# UPCH.net
KiCad netlist of a schematic drawn in EAGLE
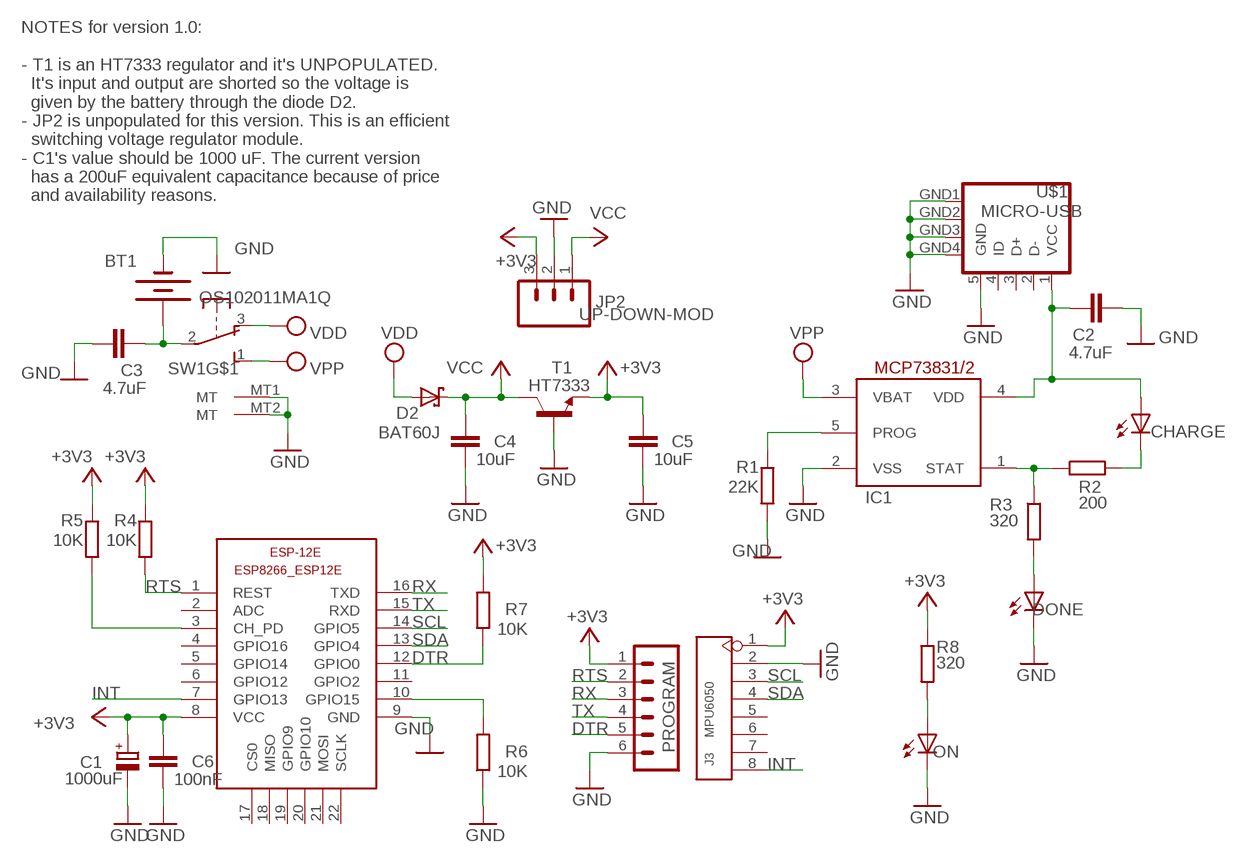
[diagram p0: schematic, sheet 1]

(export (version "E")
  (design (tool "Eeschema 10.0.6"))
  (components
    (comp (ref "BT1")
      (value "BATTERY24.5MM")
      (footprint "eagle-import:BATTCON_24.5MM")
      (libsource (lib "eagle-import") (part "BATTERY24.5MM"))
    )
    (comp (ref "C1")
      (value "1000uF")
      (footprint "eagle-import:D_7343-31W")
      (libsource (lib "eagle-import") (part "CPOL-EUD/7343-31W"))
    )
    (comp (ref "C2")
      (value "4.7uF")
      (footprint "eagle-import:C1206")
      (libsource (lib "eagle-import") (part "C-EUC1206"))
    )
    (comp (ref "C3")
      (value "4.7uF")
      (footprint "eagle-import:C1206")
      (libsource (lib "eagle-import") (part "C-EUC1206"))
    )
    (comp (ref "C4")
      (value "10uF")
      (footprint "eagle-import:C1206")
      (libsource (lib "eagle-import") (part "C-EUC1206"))
    )
    (comp (ref "C5")
      (value "10uF")
      (footprint "eagle-import:C1206")
      (libsource (lib "eagle-import") (part "C-EUC1206"))
    )
    (comp (ref "C6")
      (value "100nF")
      (footprint "eagle-import:C1206")
      (libsource (lib "eagle-import") (part "C-EUC1206"))
    )
    (comp (ref "CHARGE")
      (value "LEDCHIP-LED0603")
      (footprint "eagle-import:CHIP-LED0603")
      (libsource (lib "eagle-import") (part "LEDCHIP-LED0603"))
    )
    (comp (ref "D2")
      (value "BAT60J")
      (footprint "eagle-import:SOD323_ST")
      (libsource (lib "eagle-import") (part "BAT60J"))
    )
    (comp (ref "DONE")
      (value "LEDCHIP-LED0603")
      (footprint "eagle-import:CHIP-LED0603")
      (libsource (lib "eagle-import") (part "LEDCHIP-LED0603"))
    )
    (comp (ref "ESP-12E")
      (value "ESP8266-12EESP8266-ESP12E")
      (footprint "eagle-import:ESP8266-ESP12E")
      (libsource (lib "eagle-import") (part "ESP8266-12EESP8266-ESP12E"))
    )
    (comp (ref "IC1")
      (value "MCP73831")
      (footprint "eagle-import:SOT23-5L")
      (libsource (lib "eagle-import") (part "MCP73831/OT"))
    )
    (comp (ref "J3")
      (value "MPU6050")
      (footprint "eagle-import:H8-SMD-2.54-90D")
      (fields (field (name "MPN") "F185-1108A0BZYA1"))
      (libsource (lib "eagle-import") (part "SMD-BLACK-FEMALE-HEADER(8P-2.54-90D)"))
    )
    (comp (ref "JP2")
      (value "UP-DOWN-MOD")
      (footprint "eagle-import:1X03")
      (libsource (lib "eagle-import") (part "M03PTH"))
    )
    (comp (ref "ON")
      (value "LEDCHIP-LED0603")
      (footprint "eagle-import:CHIP-LED0603")
      (libsource (lib "eagle-import") (part "LEDCHIP-LED0603"))
    )
    (comp (ref "PROGRAM")
      (value "CONN_06SILK_FEMALE_PTH")
      (footprint "eagle-import:1X06")
      (libsource (lib "eagle-import") (part "CONN_06SILK_FEMALE_PTH"))
    )
    (comp (ref "R1")
      (value "22K")
      (footprint "eagle-import:R0603")
      (libsource (lib "eagle-import") (part "R-EU_R0603"))
    )
    (comp (ref "R2")
      (value "200")
      (footprint "eagle-import:R1206")
      (libsource (lib "eagle-import") (part "R-EU_R1206"))
    )
    (comp (ref "R3")
      (value "320")
      (footprint "eagle-import:R0603")
      (libsource (lib "eagle-import") (part "R-EU_R0603"))
    )
    (comp (ref "R4")
      (value "10K")
      (footprint "eagle-import:R0603")
      (libsource (lib "eagle-import") (part "R-EU_R0603"))
    )
    (comp (ref "R5")
      (value "10K")
      (footprint "eagle-import:R0603")
      (libsource (lib "eagle-import") (part "R-EU_R0603"))
    )
    (comp (ref "R6")
      (value "10K")
      (footprint "eagle-import:R0603")
      (libsource (lib "eagle-import") (part "R-EU_R0603"))
    )
    (comp (ref "R7")
      (value "10K")
      (footprint "eagle-import:R1206")
      (libsource (lib "eagle-import") (part "R-EU_R1206"))
    )
    (comp (ref "R8")
      (value "320")
      (footprint "eagle-import:R0603")
      (libsource (lib "eagle-import") (part "R-EU_R0603"))
    )
    (comp (ref "SW1")
      (value "OS102011MA1Q")
      (footprint "eagle-import:OS102011MA1Q")
      (libsource (lib "eagle-import") (part "OS102011MA1Q"))
    )
    (comp (ref "T1")
      (value "HT7333")
      (footprint "eagle-import:SOT89-BCE")
      (libsource (lib "eagle-import") (part "-NPN-SOT89-BCE"))
    )
    (comp (ref "U$1")
      (value "MICRO-USB")
      (footprint "eagle-import:MICRO-USB")
      (libsource (lib "eagle-import") (part "MICRO-USB"))
    )
  )
  (nets
    (net (code "1") (name "+3V3") (class "Default")
      (node (ref "C1") (pin "+") (pinfunction "+_+") (pintype "passive"))
      (node (ref "C5") (pin "1") (pinfunction "1_1") (pintype "passive"))
      (node (ref "C6") (pin "1") (pinfunction "1_1") (pintype "passive"))
      (node (ref "ESP-12E") (pin "8") (pinfunction "VCC_8") (pintype "bidirectional"))
      (node (ref "J3") (pin "1") (pinfunction "1_1") (pintype "bidirectional"))
      (node (ref "JP2") (pin "3") (pinfunction "3_3") (pintype "passive"))
      (node (ref "PROGRAM") (pin "1") (pinfunction "1_1") (pintype "passive"))
      (node (ref "R4") (pin "2") (pinfunction "2_2") (pintype "passive"))
      (node (ref "R5") (pin "2") (pinfunction "2_2") (pintype "passive"))
      (node (ref "R7") (pin "2") (pinfunction "2_2") (pintype "passive"))
      (node (ref "R8") (pin "1") (pinfunction "1_1") (pintype "passive"))
      (node (ref "T1") (pin "E") (pinfunction "E_E") (pintype "passive"))
    )
    (net (code "2") (name "/DTR") (class "Default")
      (node (ref "ESP-12E") (pin "12") (pinfunction "GPIO0_12") (pintype "bidirectional"))
      (node (ref "PROGRAM") (pin "5") (pinfunction "5_5") (pintype "passive"))
      (node (ref "R7") (pin "1") (pinfunction "1_1") (pintype "passive"))
    )
    (net (code "3") (name "/INT") (class "Default")
      (node (ref "ESP-12E") (pin "7") (pinfunction "GPIO13_7") (pintype "bidirectional"))
      (node (ref "J3") (pin "8") (pinfunction "8_8") (pintype "bidirectional"))
    )
    (net (code "4") (name "/RTS") (class "Default")
      (node (ref "ESP-12E") (pin "1") (pinfunction "REST_1") (pintype "bidirectional"))
      (node (ref "PROGRAM") (pin "2") (pinfunction "2_2") (pintype "passive"))
      (node (ref "R4") (pin "1") (pinfunction "1_1") (pintype "passive"))
    )
    (net (code "5") (name "/RX") (class "Default")
      (node (ref "ESP-12E") (pin "16") (pinfunction "TXD_16") (pintype "bidirectional"))
      (node (ref "PROGRAM") (pin "3") (pinfunction "3_3") (pintype "passive"))
    )
    (net (code "6") (name "/SCL") (class "Default")
      (node (ref "ESP-12E") (pin "14") (pinfunction "GPIO5_14") (pintype "bidirectional"))
      (node (ref "J3") (pin "3") (pinfunction "3_3") (pintype "bidirectional"))
    )
    (net (code "7") (name "/SDA") (class "Default")
      (node (ref "ESP-12E") (pin "13") (pinfunction "GPIO4_13") (pintype "bidirectional"))
      (node (ref "J3") (pin "4") (pinfunction "4_4") (pintype "bidirectional"))
    )
    (net (code "8") (name "/TX") (class "Default")
      (node (ref "ESP-12E") (pin "15") (pinfunction "RXD_15") (pintype "bidirectional"))
      (node (ref "PROGRAM") (pin "4") (pinfunction "4_4") (pintype "passive"))
    )
    (net (code "9") (name "GND") (class "Default")
      (node (ref "BT1") (pin "2") (pinfunction "-_2") (pintype "power_in"))
      (node (ref "C1") (pin "-") (pinfunction "-_-") (pintype "passive"))
      (node (ref "C2") (pin "2") (pinfunction "2_2") (pintype "passive"))
      (node (ref "C3") (pin "2") (pinfunction "2_2") (pintype "passive"))
      (node (ref "C4") (pin "2") (pinfunction "2_2") (pintype "passive"))
      (node (ref "C5") (pin "2") (pinfunction "2_2") (pintype "passive"))
      (node (ref "C6") (pin "2") (pinfunction "2_2") (pintype "passive"))
      (node (ref "DONE") (pin "C") (pinfunction "C_C") (pintype "passive"))
      (node (ref "ESP-12E") (pin "9") (pinfunction "GND_9") (pintype "bidirectional"))
      (node (ref "IC1") (pin "2") (pinfunction "VSS_2") (pintype "power_in"))
      (node (ref "J3") (pin "2") (pinfunction "2_2") (pintype "bidirectional"))
      (node (ref "JP2") (pin "2") (pinfunction "2_2") (pintype "passive"))
      (node (ref "ON") (pin "C") (pinfunction "C_C") (pintype "passive"))
      (node (ref "PROGRAM") (pin "6") (pinfunction "6_6") (pintype "passive"))
      (node (ref "R1") (pin "1") (pinfunction "1_1") (pintype "passive"))
      (node (ref "R6") (pin "1") (pinfunction "1_1") (pintype "passive"))
      (node (ref "SW1") (pin "MT1") (pinfunction "MT_MT1") (pintype "passive"))
      (node (ref "SW1") (pin "MT2") (pinfunction "MT_MT2") (pintype "passive"))
      (node (ref "T1") (pin "B") (pinfunction "B_B") (pintype "passive"))
      (node (ref "U$1") (pin "5") (pinfunction "GND_5") (pintype "power_in"))
      (node (ref "U$1") (pin "GND1") (pinfunction "GND_GND1") (pintype "power_in"))
      (node (ref "U$1") (pin "GND2") (pinfunction "GND_GND2") (pintype "power_in"))
      (node (ref "U$1") (pin "GND3") (pinfunction "GND_GND3") (pintype "power_in"))
      (node (ref "U$1") (pin "GND4") (pinfunction "GND_GND4") (pintype "power_in"))
    )
    (net (code "10") (name "Net-(BT1-+)") (class "Default")
      (node (ref "BT1") (pin "1") (pinfunction "+_1") (pintype "power_in"))
      (node (ref "C3") (pin "1") (pinfunction "1_1") (pintype "passive"))
      (node (ref "SW1") (pin "2") (pinfunction "P_2") (pintype "passive"))
    )
    (net (code "11") (name "Net-(CHARGE-PadC)") (class "Default")
      (node (ref "CHARGE") (pin "C") (pinfunction "C_C") (pintype "passive"))
      (node (ref "R2") (pin "2") (pinfunction "2_2") (pintype "passive"))
    )
    (net (code "12") (name "Net-(DONE-PadA)") (class "Default")
      (node (ref "DONE") (pin "A") (pinfunction "A_A") (pintype "passive"))
      (node (ref "R3") (pin "2") (pinfunction "2_2") (pintype "passive"))
    )
    (net (code "13") (name "Net-(ESP-12E-CH_PD)") (class "Default")
      (node (ref "ESP-12E") (pin "3") (pinfunction "CH_PD_3") (pintype "bidirectional"))
      (node (ref "R5") (pin "1") (pinfunction "1_1") (pintype "passive"))
    )
    (net (code "14") (name "Net-(ESP-12E-GPIO15)") (class "Default")
      (node (ref "ESP-12E") (pin "10") (pinfunction "GPIO15_10") (pintype "bidirectional"))
      (node (ref "R6") (pin "2") (pinfunction "2_2") (pintype "passive"))
    )
    (net (code "15") (name "Net-(IC1-PROG)") (class "Default")
      (node (ref "IC1") (pin "5") (pinfunction "PROG_5") (pintype "input"))
      (node (ref "R1") (pin "2") (pinfunction "2_2") (pintype "passive"))
    )
    (net (code "16") (name "Net-(IC1-STAT)") (class "Default")
      (node (ref "IC1") (pin "1") (pinfunction "STAT_1") (pintype "output"))
      (node (ref "R2") (pin "1") (pinfunction "1_1") (pintype "passive"))
      (node (ref "R3") (pin "1") (pinfunction "1_1") (pintype "passive"))
    )
    (net (code "17") (name "Net-(IC1-VDD)") (class "Default")
      (node (ref "C2") (pin "1") (pinfunction "1_1") (pintype "passive"))
      (node (ref "CHARGE") (pin "A") (pinfunction "A_A") (pintype "passive"))
      (node (ref "IC1") (pin "4") (pinfunction "VDD_4") (pintype "power_in"))
      (node (ref "U$1") (pin "1") (pinfunction "VCC_1") (pintype "power_in"))
    )
    (net (code "18") (name "Net-(ON-PadA)") (class "Default")
      (node (ref "ON") (pin "A") (pinfunction "A_A") (pintype "passive"))
      (node (ref "R8") (pin "2") (pinfunction "2_2") (pintype "passive"))
    )
    (net (code "19") (name "VCC") (class "Default")
      (node (ref "C4") (pin "1") (pinfunction "1_1") (pintype "passive"))
      (node (ref "D2") (pin "C") (pinfunction "C_C") (pintype "passive"))
      (node (ref "JP2") (pin "1") (pinfunction "1_1") (pintype "passive"))
      (node (ref "T1") (pin "C") (pinfunction "C_C") (pintype "passive"))
    )
    (net (code "20") (name "VDD") (class "Default")
      (node (ref "D2") (pin "A") (pinfunction "A_A") (pintype "passive"))
      (node (ref "SW1") (pin "3") (pinfunction "O_3") (pintype "passive"))
    )
    (net (code "21") (name "VPP") (class "Default")
      (node (ref "IC1") (pin "3") (pinfunction "VBAT_3") (pintype "bidirectional"))
      (node (ref "SW1") (pin "1") (pinfunction "S_1") (pintype "passive"))
    )
    (net (code "22") (name "unconnected-(ESP-12E-ADC-Pad2)") (class "Default")
      (node (ref "ESP-12E") (pin "2") (pinfunction "ADC_2") (pintype "bidirectional"))
    )
    (net (code "23") (name "unconnected-(ESP-12E-CS0-Pad17)") (class "Default")
      (node (ref "ESP-12E") (pin "17") (pinfunction "CS0_17") (pintype "bidirectional"))
    )
    (net (code "24") (name "unconnected-(ESP-12E-GPIO2-Pad11)") (class "Default")
      (node (ref "ESP-12E") (pin "11") (pinfunction "GPIO2_11") (pintype "bidirectional"))
    )
    (net (code "25") (name "unconnected-(ESP-12E-GPIO9-Pad19)") (class "Default")
      (node (ref "ESP-12E") (pin "19") (pinfunction "GPIO9_19") (pintype "bidirectional"))
    )
    (net (code "26") (name "unconnected-(ESP-12E-GPIO10-Pad20)") (class "Default")
      (node (ref "ESP-12E") (pin "20") (pinfunction "GPIO10_20") (pintype "bidirectional"))
    )
    (net (code "27") (name "unconnected-(ESP-12E-GPIO12-Pad6)") (class "Default")
      (node (ref "ESP-12E") (pin "6") (pinfunction "GPIO12_6") (pintype "bidirectional"))
    )
    (net (code "28") (name "unconnected-(ESP-12E-GPIO14-Pad5)") (class "Default")
      (node (ref "ESP-12E") (pin "5") (pinfunction "GPIO14_5") (pintype "bidirectional"))
    )
    (net (code "29") (name "unconnected-(ESP-12E-GPIO16-Pad4)") (class "Default")
      (node (ref "ESP-12E") (pin "4") (pinfunction "GPIO16_4") (pintype "bidirectional"))
    )
    (net (code "30") (name "unconnected-(ESP-12E-MISO-Pad18)") (class "Default")
      (node (ref "ESP-12E") (pin "18") (pinfunction "MISO_18") (pintype "bidirectional"))
    )
    (net (code "31") (name "unconnected-(ESP-12E-MOSI-Pad21)") (class "Default")
      (node (ref "ESP-12E") (pin "21") (pinfunction "MOSI_21") (pintype "bidirectional"))
    )
    (net (code "32") (name "unconnected-(ESP-12E-SCLK-Pad22)") (class "Default")
      (node (ref "ESP-12E") (pin "22") (pinfunction "SCLK_22") (pintype "bidirectional"))
    )
    (net (code "33") (name "unconnected-(J3-Pad5)") (class "Default")
      (node (ref "J3") (pin "5") (pinfunction "5_5") (pintype "bidirectional"))
    )
    (net (code "34") (name "unconnected-(J3-Pad6)") (class "Default")
      (node (ref "J3") (pin "6") (pinfunction "6_6") (pintype "bidirectional"))
    )
    (net (code "35") (name "unconnected-(J3-Pad7)") (class "Default")
      (node (ref "J3") (pin "7") (pinfunction "7_7") (pintype "bidirectional"))
    )
    (net (code "36") (name "unconnected-(U$1-D+-Pad3)") (class "Default")
      (node (ref "U$1") (pin "3") (pinfunction "D+_3") (pintype "bidirectional"))
    )
    (net (code "37") (name "unconnected-(U$1-D--Pad2)") (class "Default")
      (node (ref "U$1") (pin "2") (pinfunction "D-_2") (pintype "bidirectional"))
    )
    (net (code "38") (name "unconnected-(U$1-ID-Pad4)") (class "Default")
      (node (ref "U$1") (pin "4") (pinfunction "ID_4") (pintype "bidirectional"))
    )
  )
)
